# Escon_middle_board.net
KiCad netlist of a schematic drawn in EAGLE
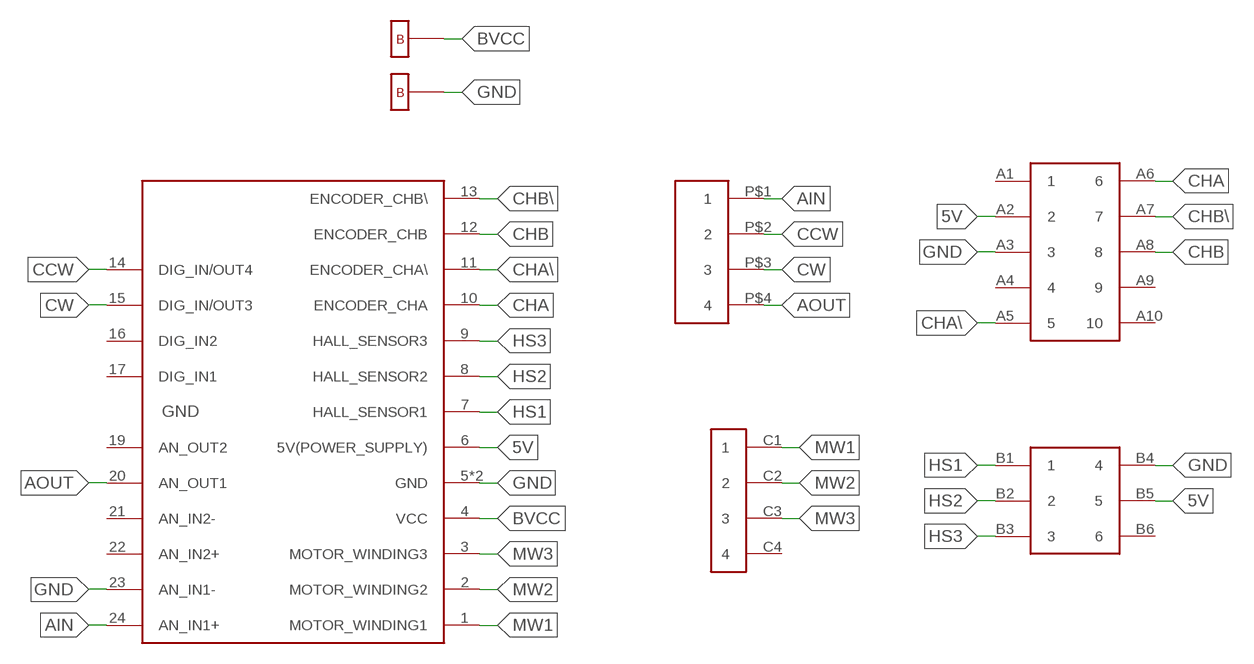
[diagram p0: schematic, sheet 1]

(export (version "E")
  (design (tool "Eeschema 10.0.6"))
  (components
    (comp (ref "U$1")
      (value "ESCON24/224/2")
      (footprint "eagle-import:ESCON24_2")
      (libsource (lib "eagle-import") (part "ESCON24/224/2"))
    )
    (comp (ref "U$2")
      (value "280378-2CONNECTOR")
      (footprint "eagle-import:280378-2CONNECTOR")
      (libsource (lib "eagle-import") (part "280378-2CONNECTOR"))
    )
    (comp (ref "U$3")
      (value "PIN2.54-2X5")
      (footprint "eagle-import:PIN2.54-2X5")
      (libsource (lib "eagle-import") (part "PIN2.54-2X5"))
    )
    (comp (ref "U$4")
      (value "MX-44914-0601")
      (footprint "eagle-import:MX-44914-0601")
      (libsource (lib "eagle-import") (part "MX-44914-0601"))
    )
    (comp (ref "U$5")
      (value "MX5566")
      (footprint "eagle-import:MX5566")
      (libsource (lib "eagle-import") (part "MX5566"))
    )
    (comp (ref "U$6")
      (value "BHOLE")
      (footprint "eagle-import:BHOLE")
      (libsource (lib "eagle-import") (part "BHOLE"))
    )
    (comp (ref "U$7")
      (value "BHOLE")
      (footprint "eagle-import:BHOLE")
      (libsource (lib "eagle-import") (part "BHOLE"))
    )
  )
  (nets
    (net (code "1") (name "5V") (class "Default")
      (node (ref "U$1") (pin "6") (pinfunction "5V(POWER_SUPPLY)_6") (pintype "bidirectional"))
      (node (ref "U$3") (pin "A2") (pinfunction "2_A2") (pintype "bidirectional"))
      (node (ref "U$4") (pin "B5") (pinfunction "5_B5") (pintype "bidirectional"))
    )
    (net (code "2") (name "AIN") (class "Default")
      (node (ref "U$1") (pin "24") (pinfunction "AN_IN1+_24") (pintype "bidirectional"))
      (node (ref "U$2") (pin "P$1") (pinfunction "1_P$1") (pintype "bidirectional"))
    )
    (net (code "3") (name "AOUT") (class "Default")
      (node (ref "U$1") (pin "20") (pinfunction "AN_OUT1_20") (pintype "bidirectional"))
      (node (ref "U$2") (pin "P$4") (pinfunction "4_P$4") (pintype "bidirectional"))
    )
    (net (code "4") (name "BVCC") (class "Default")
      (node (ref "U$1") (pin "4") (pinfunction "VCC_4") (pintype "bidirectional"))
      (node (ref "U$6") (pin "P$1") (pinfunction "P$1_P$1") (pintype "bidirectional"))
    )
    (net (code "5") (name "CCW") (class "Default")
      (node (ref "U$1") (pin "14") (pinfunction "DIG_IN/OUT4_14") (pintype "bidirectional"))
      (node (ref "U$2") (pin "P$2") (pinfunction "2_P$2") (pintype "bidirectional"))
    )
    (net (code "6") (name "CHA") (class "Default")
      (node (ref "U$1") (pin "10") (pinfunction "ENCODER_CHA_10") (pintype "bidirectional"))
      (node (ref "U$3") (pin "A6") (pinfunction "6_A6") (pintype "bidirectional"))
    )
    (net (code "7") (name "CHA\\\\") (class "Default")
      (node (ref "U$1") (pin "11") (pinfunction "ENCODER_CHA\\\\_11") (pintype "bidirectional"))
      (node (ref "U$3") (pin "A5") (pinfunction "5_A5") (pintype "bidirectional"))
    )
    (net (code "8") (name "CHB") (class "Default")
      (node (ref "U$1") (pin "12") (pinfunction "ENCODER_CHB_12") (pintype "bidirectional"))
      (node (ref "U$3") (pin "A8") (pinfunction "8_A8") (pintype "bidirectional"))
    )
    (net (code "9") (name "CHB\\\\") (class "Default")
      (node (ref "U$1") (pin "13") (pinfunction "ENCODER_CHB\\\\_13") (pintype "bidirectional"))
      (node (ref "U$3") (pin "A7") (pinfunction "7_A7") (pintype "bidirectional"))
    )
    (net (code "10") (name "CW") (class "Default")
      (node (ref "U$1") (pin "15") (pinfunction "DIG_IN/OUT3_15") (pintype "bidirectional"))
      (node (ref "U$2") (pin "P$3") (pinfunction "3_P$3") (pintype "bidirectional"))
    )
    (net (code "11") (name "GND") (class "Default")
      (node (ref "U$1") (pin "18") (pinfunction "GND_18") (pintype "bidirectional"))
      (node (ref "U$1") (pin "23") (pinfunction "AN_IN1-_23") (pintype "bidirectional"))
      (node (ref "U$1") (pin "5") (pinfunction "GND_5") (pintype "bidirectional"))
      (node (ref "U$3") (pin "A3") (pinfunction "3_A3") (pintype "bidirectional"))
      (node (ref "U$4") (pin "B4") (pinfunction "4_B4") (pintype "bidirectional"))
      (node (ref "U$7") (pin "P$1") (pinfunction "P$1_P$1") (pintype "bidirectional"))
    )
    (net (code "12") (name "HS1") (class "Default")
      (node (ref "U$1") (pin "7") (pinfunction "HALL_SENSOR1_7") (pintype "bidirectional"))
      (node (ref "U$4") (pin "B1") (pinfunction "1_B1") (pintype "bidirectional"))
    )
    (net (code "13") (name "HS2") (class "Default")
      (node (ref "U$1") (pin "8") (pinfunction "HALL_SENSOR2_8") (pintype "bidirectional"))
      (node (ref "U$4") (pin "B2") (pinfunction "2_B2") (pintype "bidirectional"))
    )
    (net (code "14") (name "HS3") (class "Default")
      (node (ref "U$1") (pin "9") (pinfunction "HALL_SENSOR3_9") (pintype "bidirectional"))
      (node (ref "U$4") (pin "B3") (pinfunction "3_B3") (pintype "bidirectional"))
    )
    (net (code "15") (name "MW1") (class "Default")
      (node (ref "U$1") (pin "1") (pinfunction "MOTOR_WINDING1_1") (pintype "bidirectional"))
      (node (ref "U$5") (pin "C1") (pinfunction "1_C1") (pintype "bidirectional"))
    )
    (net (code "16") (name "MW2") (class "Default")
      (node (ref "U$1") (pin "2") (pinfunction "MOTOR_WINDING2_2") (pintype "bidirectional"))
      (node (ref "U$5") (pin "C2") (pinfunction "2_C2") (pintype "bidirectional"))
    )
    (net (code "17") (name "MW3") (class "Default")
      (node (ref "U$1") (pin "3") (pinfunction "MOTOR_WINDING3_3") (pintype "bidirectional"))
      (node (ref "U$5") (pin "C3") (pinfunction "3_C3") (pintype "bidirectional"))
    )
    (net (code "18") (name "unconnected-(U$1-AN_IN2+-Pad22)") (class "Default")
      (node (ref "U$1") (pin "22") (pinfunction "AN_IN2+_22") (pintype "bidirectional"))
    )
    (net (code "19") (name "unconnected-(U$1-AN_IN2--Pad21)") (class "Default")
      (node (ref "U$1") (pin "21") (pinfunction "AN_IN2-_21") (pintype "bidirectional"))
    )
    (net (code "20") (name "unconnected-(U$1-AN_OUT2-Pad19)") (class "Default")
      (node (ref "U$1") (pin "19") (pinfunction "AN_OUT2_19") (pintype "bidirectional"))
    )
    (net (code "21") (name "unconnected-(U$1-DIG_IN1-Pad17)") (class "Default")
      (node (ref "U$1") (pin "17") (pinfunction "DIG_IN1_17") (pintype "bidirectional"))
    )
    (net (code "22") (name "unconnected-(U$1-DIG_IN2-Pad16)") (class "Default")
      (node (ref "U$1") (pin "16") (pinfunction "DIG_IN2_16") (pintype "bidirectional"))
    )
    (net (code "23") (name "unconnected-(U$3-1-PadA1)") (class "Default")
      (node (ref "U$3") (pin "A1") (pinfunction "1_A1") (pintype "bidirectional"))
    )
    (net (code "24") (name "unconnected-(U$3-4-PadA4)") (class "Default")
      (node (ref "U$3") (pin "A4") (pinfunction "4_A4") (pintype "bidirectional"))
    )
    (net (code "25") (name "unconnected-(U$3-9-PadA9)") (class "Default")
      (node (ref "U$3") (pin "A9") (pinfunction "9_A9") (pintype "bidirectional"))
    )
    (net (code "26") (name "unconnected-(U$3-10-PadA10)") (class "Default")
      (node (ref "U$3") (pin "A10") (pinfunction "10_A10") (pintype "bidirectional"))
    )
    (net (code "27") (name "unconnected-(U$4-6-PadB6)") (class "Default")
      (node (ref "U$4") (pin "B6") (pinfunction "6_B6") (pintype "bidirectional"))
    )
    (net (code "28") (name "unconnected-(U$5-4-PadC4)") (class "Default")
      (node (ref "U$5") (pin "C4") (pinfunction "4_C4") (pintype "bidirectional"))
    )
  )
)
